# Sheet1.net
KiCad netlist of a schematic drawn in Altium Designer
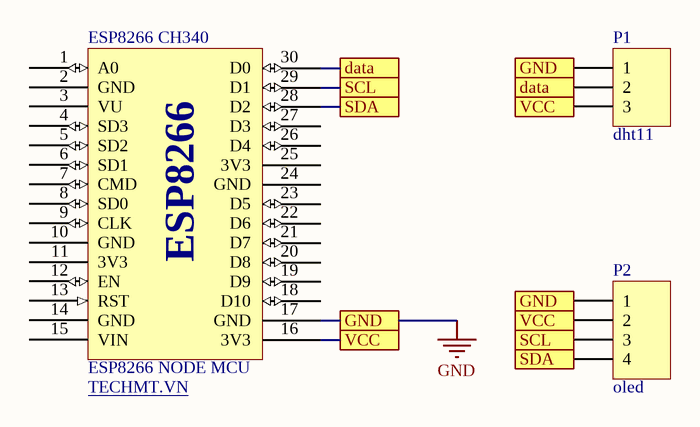
[diagram p0: Sheet1.SchDoc]

(export (version "E")
  (design (tool "Eeschema 10.0.6"))
  (components
    (comp (ref "ESP8266 CH340")
      (value "ESP8266 NODE MCU")
      (footprint "ESP8266 NodeMCU")
      (description "LUA-ESP8266 Wifi Module Techmt.vn")
      (fields (field (name "WEB") "TECHMT.VN"))
      (libsource (lib "TechMT.VN_Lib_Project v2") (part "ESP8266 NodeMCU"))
    )
    (comp (ref "P1")
      (value "dht11")
      (footprint "HDR1X3")
      (description "Header, 3-Pin")
      (fields (field (name "PUBLISHER") "Altium Limited"))
      (libsource (lib "Miscellaneous Connectors") (part "Header 3"))
    )
    (comp (ref "P2")
      (value "oled")
      (footprint "HDR1X4")
      (description "Header, 4-Pin")
      (fields (field (name "PUBLISHER") "Altium Limited"))
      (libsource (lib "Miscellaneous Connectors") (part "Header 4"))
    )
  )
  (nets
    (net (code "1") (name "/SCL") (class "Default")
      (node (ref "ESP8266 CH340") (pin "29") (pinfunction "D1_29") (pintype "bidirectional"))
      (node (ref "P2") (pin "3") (pinfunction "3_3") (pintype "passive"))
    )
    (net (code "2") (name "/SDA") (class "Default")
      (node (ref "ESP8266 CH340") (pin "28") (pinfunction "D2_28") (pintype "bidirectional"))
      (node (ref "P2") (pin "4") (pinfunction "4_4") (pintype "passive"))
    )
    (net (code "3") (name "/VCC") (class "Default")
      (node (ref "ESP8266 CH340") (pin "16") (pinfunction "3V3_16") (pintype "power_in"))
      (node (ref "P1") (pin "3") (pinfunction "3_3") (pintype "passive"))
      (node (ref "P2") (pin "2") (pinfunction "2_2") (pintype "passive"))
    )
    (net (code "4") (name "/data") (class "Default")
      (node (ref "ESP8266 CH340") (pin "30") (pinfunction "D0_30") (pintype "bidirectional"))
      (node (ref "P1") (pin "2") (pinfunction "2_2") (pintype "passive"))
    )
    (net (code "5") (name "GND") (class "Default")
      (node (ref "ESP8266 CH340") (pin "17") (pinfunction "GND_17") (pintype "power_in"))
      (node (ref "P1") (pin "1") (pinfunction "1_1") (pintype "passive"))
      (node (ref "P2") (pin "1") (pinfunction "1_1") (pintype "passive"))
    )
    (net (code "6") (name "unconnected-(ESP8266 CH340-3V3-Pad11)") (class "Default")
      (node (ref "ESP8266 CH340") (pin "11") (pinfunction "3V3_11") (pintype "power_in"))
    )
    (net (code "7") (name "unconnected-(ESP8266 CH340-3V3-Pad25)") (class "Default")
      (node (ref "ESP8266 CH340") (pin "25") (pinfunction "3V3_25") (pintype "power_in"))
    )
    (net (code "8") (name "unconnected-(ESP8266 CH340-A0-Pad1)") (class "Default")
      (node (ref "ESP8266 CH340") (pin "1") (pinfunction "A0_1") (pintype "bidirectional"))
    )
    (net (code "9") (name "unconnected-(ESP8266 CH340-CLK-Pad9)") (class "Default")
      (node (ref "ESP8266 CH340") (pin "9") (pinfunction "CLK_9") (pintype "bidirectional"))
    )
    (net (code "10") (name "unconnected-(ESP8266 CH340-CMD-Pad7)") (class "Default")
      (node (ref "ESP8266 CH340") (pin "7") (pinfunction "CMD_7") (pintype "bidirectional"))
    )
    (net (code "11") (name "unconnected-(ESP8266 CH340-D3-Pad27)") (class "Default")
      (node (ref "ESP8266 CH340") (pin "27") (pinfunction "D3_27") (pintype "bidirectional"))
    )
    (net (code "12") (name "unconnected-(ESP8266 CH340-D4-Pad26)") (class "Default")
      (node (ref "ESP8266 CH340") (pin "26") (pinfunction "D4_26") (pintype "bidirectional"))
    )
    (net (code "13") (name "unconnected-(ESP8266 CH340-D5-Pad23)") (class "Default")
      (node (ref "ESP8266 CH340") (pin "23") (pinfunction "D5_23") (pintype "bidirectional"))
    )
    (net (code "14") (name "unconnected-(ESP8266 CH340-D6-Pad22)") (class "Default")
      (node (ref "ESP8266 CH340") (pin "22") (pinfunction "D6_22") (pintype "bidirectional"))
    )
    (net (code "15") (name "unconnected-(ESP8266 CH340-D7-Pad21)") (class "Default")
      (node (ref "ESP8266 CH340") (pin "21") (pinfunction "D7_21") (pintype "bidirectional"))
    )
    (net (code "16") (name "unconnected-(ESP8266 CH340-D8-Pad20)") (class "Default")
      (node (ref "ESP8266 CH340") (pin "20") (pinfunction "D8_20") (pintype "bidirectional"))
    )
    (net (code "17") (name "unconnected-(ESP8266 CH340-D9-Pad19)") (class "Default")
      (node (ref "ESP8266 CH340") (pin "19") (pinfunction "D9_19") (pintype "bidirectional"))
    )
    (net (code "18") (name "unconnected-(ESP8266 CH340-D10-Pad18)") (class "Default")
      (node (ref "ESP8266 CH340") (pin "18") (pinfunction "D10_18") (pintype "bidirectional"))
    )
    (net (code "19") (name "unconnected-(ESP8266 CH340-EN-Pad12)") (class "Default")
      (node (ref "ESP8266 CH340") (pin "12") (pinfunction "EN_12") (pintype "bidirectional"))
    )
    (net (code "20") (name "unconnected-(ESP8266 CH340-GND-Pad2)") (class "Default")
      (node (ref "ESP8266 CH340") (pin "2") (pinfunction "GND_2") (pintype "power_in"))
    )
    (net (code "21") (name "unconnected-(ESP8266 CH340-GND-Pad10)") (class "Default")
      (node (ref "ESP8266 CH340") (pin "10") (pinfunction "GND_10") (pintype "power_in"))
    )
    (net (code "22") (name "unconnected-(ESP8266 CH340-GND-Pad14)") (class "Default")
      (node (ref "ESP8266 CH340") (pin "14") (pinfunction "GND_14") (pintype "power_in"))
    )
    (net (code "23") (name "unconnected-(ESP8266 CH340-GND-Pad24)") (class "Default")
      (node (ref "ESP8266 CH340") (pin "24") (pinfunction "GND_24") (pintype "power_in"))
    )
    (net (code "24") (name "unconnected-(ESP8266 CH340-RST-Pad13)") (class "Default")
      (node (ref "ESP8266 CH340") (pin "13") (pinfunction "RST_13") (pintype "input"))
    )
    (net (code "25") (name "unconnected-(ESP8266 CH340-SD0-Pad8)") (class "Default")
      (node (ref "ESP8266 CH340") (pin "8") (pinfunction "SD0_8") (pintype "bidirectional"))
    )
    (net (code "26") (name "unconnected-(ESP8266 CH340-SD1-Pad6)") (class "Default")
      (node (ref "ESP8266 CH340") (pin "6") (pinfunction "SD1_6") (pintype "bidirectional"))
    )
    (net (code "27") (name "unconnected-(ESP8266 CH340-SD2-Pad5)") (class "Default")
      (node (ref "ESP8266 CH340") (pin "5") (pinfunction "SD2_5") (pintype "bidirectional"))
    )
    (net (code "28") (name "unconnected-(ESP8266 CH340-SD3-Pad4)") (class "Default")
      (node (ref "ESP8266 CH340") (pin "4") (pinfunction "SD3_4") (pintype "bidirectional"))
    )
    (net (code "29") (name "unconnected-(ESP8266 CH340-VIN-Pad15)") (class "Default")
      (node (ref "ESP8266 CH340") (pin "15") (pinfunction "VIN_15") (pintype "power_in"))
    )
    (net (code "30") (name "unconnected-(ESP8266 CH340-VU-Pad3)") (class "Default")
      (node (ref "ESP8266 CH340") (pin "3") (pinfunction "VU_3") (pintype "power_in"))
    )
  )
)
